# edlinv.net
KiCad netlist of a schematic drawn in EAGLE
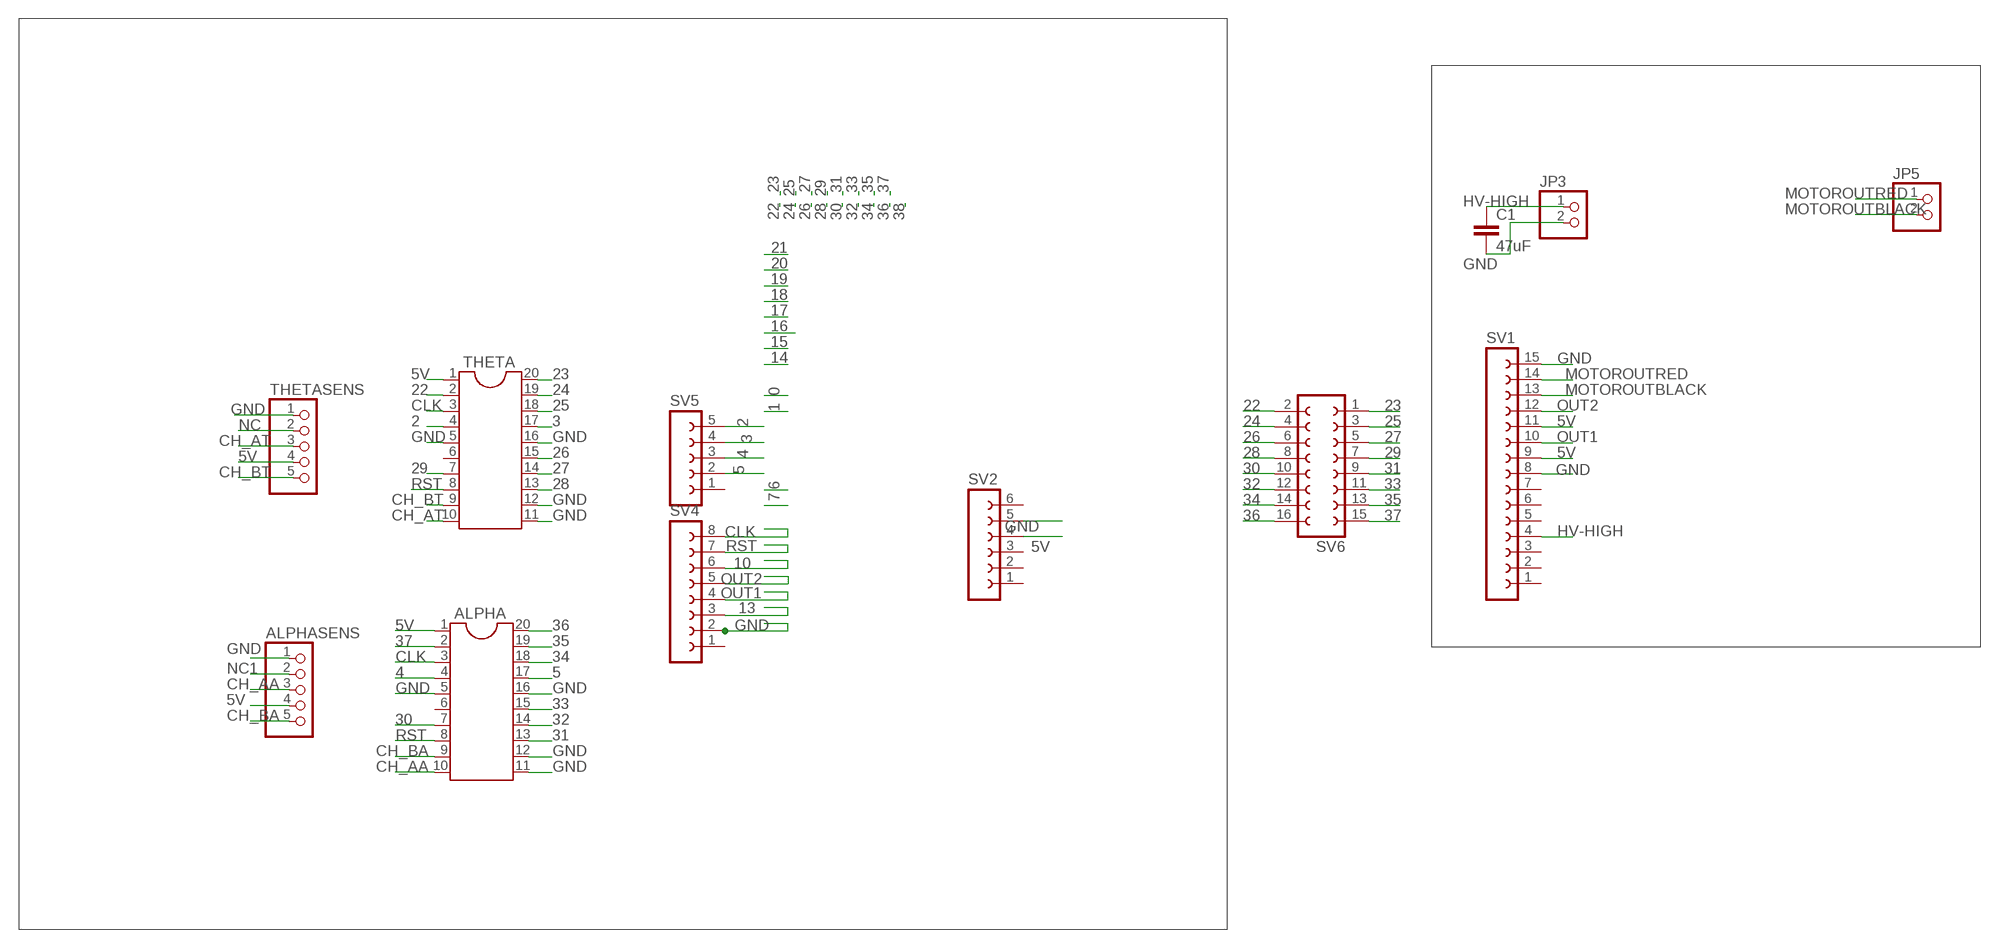
[diagram p0: schematic, sheet 1]

(export (version "E")
  (design (tool "Eeschema 10.0.6"))
  (components
    (comp (ref "ALPHA")
      (value "DIL20")
      (footprint "eagle-import:DIL20")
      (libsource (lib "eagle-import") (part "DIL20"))
    )
    (comp (ref "ALPHASENS")
      (value "PINHD-1X5")
      (footprint "eagle-import:1X05")
      (libsource (lib "eagle-import") (part "PINHD-1X5"))
    )
    (comp (ref "C1")
      (value "47uF")
      (footprint "eagle-import:C025-025X050")
      (libsource (lib "eagle-import") (part "C-EU025-025X050"))
    )
    (comp (ref "JP3")
      (value "PINHD-1X2")
      (footprint "eagle-import:1X02")
      (libsource (lib "eagle-import") (part "PINHD-1X2"))
    )
    (comp (ref "JP5")
      (value "PINHD-1X2")
      (footprint "eagle-import:1X02")
      (libsource (lib "eagle-import") (part "PINHD-1X2"))
    )
    (comp (ref "SV1")
      (value "FE15-1")
      (footprint "eagle-import:FE15")
      (libsource (lib "eagle-import") (part "FE15-1"))
    )
    (comp (ref "SV2")
      (value "FE06-1")
      (footprint "eagle-import:FE06")
      (libsource (lib "eagle-import") (part "FE06-1"))
    )
    (comp (ref "SV4")
      (value "FE08-1")
      (footprint "eagle-import:FE08")
      (libsource (lib "eagle-import") (part "FE08-1"))
    )
    (comp (ref "SV5")
      (value "FE05-1")
      (footprint "eagle-import:FE05-1")
      (libsource (lib "eagle-import") (part "FE05-1"))
    )
    (comp (ref "SV6")
      (value "FE08-2")
      (footprint "eagle-import:FE08-2")
      (libsource (lib "eagle-import") (part "FE08-2"))
    )
    (comp (ref "THETA")
      (value "DIL20")
      (footprint "eagle-import:DIL20")
      (libsource (lib "eagle-import") (part "DIL20"))
    )
    (comp (ref "THETASENS")
      (value "PINHD-1X5")
      (footprint "eagle-import:1X05")
      (libsource (lib "eagle-import") (part "PINHD-1X5"))
    )
  )
  (nets
    (net (code "3") (name "/2") (class "Default")
      (node (ref "SV5") (pin "5") (pinfunction "5_5") (pintype "passive"))
      (node (ref "THETA") (pin "4") (pinfunction "4_4") (pintype "passive"))
    )
    (net (code "4") (name "/3") (class "Default")
      (node (ref "SV5") (pin "4") (pinfunction "4_4") (pintype "passive"))
      (node (ref "THETA") (pin "17") (pinfunction "17_17") (pintype "passive"))
    )
    (net (code "5") (name "/4") (class "Default")
      (node (ref "ALPHA") (pin "4") (pinfunction "4_4") (pintype "passive"))
      (node (ref "SV5") (pin "3") (pinfunction "3_3") (pintype "passive"))
    )
    (net (code "6") (name "/5") (class "Default")
      (node (ref "ALPHA") (pin "17") (pinfunction "17_17") (pintype "passive"))
      (node (ref "SV5") (pin "2") (pinfunction "2_2") (pintype "passive"))
    )
    (net (code "7") (name "/5V") (class "Default")
      (node (ref "ALPHA") (pin "1") (pinfunction "1_1") (pintype "passive"))
      (node (ref "ALPHASENS") (pin "4") (pinfunction "4_4") (pintype "passive"))
      (node (ref "SV1") (pin "11") (pinfunction "11_11") (pintype "passive"))
      (node (ref "SV1") (pin "9") (pinfunction "9_9") (pintype "passive"))
      (node (ref "SV2") (pin "4") (pinfunction "4_4") (pintype "passive"))
      (node (ref "THETA") (pin "1") (pinfunction "1_1") (pintype "passive"))
      (node (ref "THETASENS") (pin "4") (pinfunction "4_4") (pintype "passive"))
    )
    (net (code "10") (name "/10") (class "Default")
      (node (ref "SV4") (pin "6") (pinfunction "6_6") (pintype "passive"))
    )
    (net (code "11") (name "/13") (class "Default")
      (node (ref "SV4") (pin "3") (pinfunction "3_3") (pintype "passive"))
    )
    (net (code "20") (name "/22") (class "Default")
      (node (ref "SV6") (pin "2") (pinfunction "2_2") (pintype "passive"))
      (node (ref "THETA") (pin "2") (pinfunction "2_2") (pintype "passive"))
    )
    (net (code "21") (name "/23") (class "Default")
      (node (ref "SV6") (pin "1") (pinfunction "1_1") (pintype "passive"))
      (node (ref "THETA") (pin "20") (pinfunction "20_20") (pintype "passive"))
    )
    (net (code "22") (name "/24") (class "Default")
      (node (ref "SV6") (pin "4") (pinfunction "4_4") (pintype "passive"))
      (node (ref "THETA") (pin "19") (pinfunction "19_19") (pintype "passive"))
    )
    (net (code "23") (name "/25") (class "Default")
      (node (ref "SV6") (pin "3") (pinfunction "3_3") (pintype "passive"))
      (node (ref "THETA") (pin "18") (pinfunction "18_18") (pintype "passive"))
    )
    (net (code "24") (name "/26") (class "Default")
      (node (ref "SV6") (pin "6") (pinfunction "6_6") (pintype "passive"))
      (node (ref "THETA") (pin "15") (pinfunction "15_15") (pintype "passive"))
    )
    (net (code "25") (name "/27") (class "Default")
      (node (ref "SV6") (pin "5") (pinfunction "5_5") (pintype "passive"))
      (node (ref "THETA") (pin "14") (pinfunction "14_14") (pintype "passive"))
    )
    (net (code "26") (name "/28") (class "Default")
      (node (ref "SV6") (pin "8") (pinfunction "8_8") (pintype "passive"))
      (node (ref "THETA") (pin "13") (pinfunction "13_13") (pintype "passive"))
    )
    (net (code "27") (name "/29") (class "Default")
      (node (ref "SV6") (pin "7") (pinfunction "7_7") (pintype "passive"))
      (node (ref "THETA") (pin "7") (pinfunction "7_7") (pintype "passive"))
    )
    (net (code "28") (name "/30") (class "Default")
      (node (ref "ALPHA") (pin "7") (pinfunction "7_7") (pintype "passive"))
      (node (ref "SV6") (pin "10") (pinfunction "10_10") (pintype "passive"))
    )
    (net (code "29") (name "/31") (class "Default")
      (node (ref "ALPHA") (pin "13") (pinfunction "13_13") (pintype "passive"))
      (node (ref "SV6") (pin "9") (pinfunction "9_9") (pintype "passive"))
    )
    (net (code "30") (name "/32") (class "Default")
      (node (ref "ALPHA") (pin "14") (pinfunction "14_14") (pintype "passive"))
      (node (ref "SV6") (pin "12") (pinfunction "12_12") (pintype "passive"))
    )
    (net (code "31") (name "/33") (class "Default")
      (node (ref "ALPHA") (pin "15") (pinfunction "15_15") (pintype "passive"))
      (node (ref "SV6") (pin "11") (pinfunction "11_11") (pintype "passive"))
    )
    (net (code "32") (name "/34") (class "Default")
      (node (ref "ALPHA") (pin "18") (pinfunction "18_18") (pintype "passive"))
      (node (ref "SV6") (pin "14") (pinfunction "14_14") (pintype "passive"))
    )
    (net (code "33") (name "/35") (class "Default")
      (node (ref "ALPHA") (pin "19") (pinfunction "19_19") (pintype "passive"))
      (node (ref "SV6") (pin "13") (pinfunction "13_13") (pintype "passive"))
    )
    (net (code "34") (name "/36") (class "Default")
      (node (ref "ALPHA") (pin "20") (pinfunction "20_20") (pintype "passive"))
      (node (ref "SV6") (pin "16") (pinfunction "16_16") (pintype "passive"))
    )
    (net (code "35") (name "/37") (class "Default")
      (node (ref "ALPHA") (pin "2") (pinfunction "2_2") (pintype "passive"))
      (node (ref "SV6") (pin "15") (pinfunction "15_15") (pintype "passive"))
    )
    (net (code "37") (name "/CH_AA") (class "Default")
      (node (ref "ALPHA") (pin "10") (pinfunction "10_10") (pintype "passive"))
      (node (ref "ALPHASENS") (pin "3") (pinfunction "3_3") (pintype "passive"))
    )
    (net (code "38") (name "/CH_AT") (class "Default")
      (node (ref "THETA") (pin "10") (pinfunction "10_10") (pintype "passive"))
      (node (ref "THETASENS") (pin "3") (pinfunction "3_3") (pintype "passive"))
    )
    (net (code "39") (name "/CH_BA") (class "Default")
      (node (ref "ALPHA") (pin "9") (pinfunction "9_9") (pintype "passive"))
      (node (ref "ALPHASENS") (pin "5") (pinfunction "5_5") (pintype "passive"))
    )
    (net (code "40") (name "/CH_BT") (class "Default")
      (node (ref "THETA") (pin "9") (pinfunction "9_9") (pintype "passive"))
      (node (ref "THETASENS") (pin "5") (pinfunction "5_5") (pintype "passive"))
    )
    (net (code "41") (name "/CLK") (class "Default")
      (node (ref "ALPHA") (pin "3") (pinfunction "3_3") (pintype "passive"))
      (node (ref "SV4") (pin "8") (pinfunction "8_8") (pintype "passive"))
      (node (ref "THETA") (pin "3") (pinfunction "3_3") (pintype "passive"))
    )
    (net (code "42") (name "/GND") (class "Default")
      (node (ref "ALPHA") (pin "11") (pinfunction "11_11") (pintype "passive"))
      (node (ref "ALPHA") (pin "12") (pinfunction "12_12") (pintype "passive"))
      (node (ref "ALPHA") (pin "16") (pinfunction "16_16") (pintype "passive"))
      (node (ref "ALPHA") (pin "5") (pinfunction "5_5") (pintype "passive"))
      (node (ref "ALPHASENS") (pin "1") (pinfunction "1_1") (pintype "passive"))
      (node (ref "C1") (pin "2") (pinfunction "2_2") (pintype "passive"))
      (node (ref "JP3") (pin "2") (pinfunction "2_2") (pintype "passive"))
      (node (ref "SV1") (pin "15") (pinfunction "15_15") (pintype "passive"))
      (node (ref "SV1") (pin "8") (pinfunction "8_8") (pintype "passive"))
      (node (ref "SV2") (pin "5") (pinfunction "5_5") (pintype "passive"))
      (node (ref "SV4") (pin "2") (pinfunction "2_2") (pintype "passive"))
      (node (ref "THETA") (pin "11") (pinfunction "11_11") (pintype "passive"))
      (node (ref "THETA") (pin "12") (pinfunction "12_12") (pintype "passive"))
      (node (ref "THETA") (pin "16") (pinfunction "16_16") (pintype "passive"))
      (node (ref "THETA") (pin "5") (pinfunction "5_5") (pintype "passive"))
      (node (ref "THETASENS") (pin "1") (pinfunction "1_1") (pintype "passive"))
    )
    (net (code "43") (name "/HV-HIGH") (class "Default")
      (node (ref "C1") (pin "1") (pinfunction "1_1") (pintype "passive"))
      (node (ref "JP3") (pin "1") (pinfunction "1_1") (pintype "passive"))
      (node (ref "SV1") (pin "4") (pinfunction "4_4") (pintype "passive"))
    )
    (net (code "44") (name "/MOTOROUTBLACK") (class "Default")
      (node (ref "JP5") (pin "2") (pinfunction "2_2") (pintype "passive"))
      (node (ref "SV1") (pin "13") (pinfunction "13_13") (pintype "passive"))
    )
    (net (code "45") (name "/MOTOROUTRED") (class "Default")
      (node (ref "JP5") (pin "1") (pinfunction "1_1") (pintype "passive"))
      (node (ref "SV1") (pin "14") (pinfunction "14_14") (pintype "passive"))
    )
    (net (code "46") (name "/NC") (class "Default")
      (node (ref "THETASENS") (pin "2") (pinfunction "2_2") (pintype "passive"))
    )
    (net (code "47") (name "/NC1") (class "Default")
      (node (ref "ALPHASENS") (pin "2") (pinfunction "2_2") (pintype "passive"))
    )
    (net (code "48") (name "/OUT1") (class "Default")
      (node (ref "SV1") (pin "10") (pinfunction "10_10") (pintype "passive"))
      (node (ref "SV4") (pin "4") (pinfunction "4_4") (pintype "passive"))
    )
    (net (code "49") (name "/OUT2") (class "Default")
      (node (ref "SV1") (pin "12") (pinfunction "12_12") (pintype "passive"))
      (node (ref "SV4") (pin "5") (pinfunction "5_5") (pintype "passive"))
    )
    (net (code "50") (name "/RST") (class "Default")
      (node (ref "ALPHA") (pin "8") (pinfunction "8_8") (pintype "passive"))
      (node (ref "SV4") (pin "7") (pinfunction "7_7") (pintype "passive"))
      (node (ref "THETA") (pin "8") (pinfunction "8_8") (pintype "passive"))
    )
    (net (code "51") (name "unconnected-(ALPHA-Pad6)") (class "Default")
      (node (ref "ALPHA") (pin "6") (pinfunction "6_6") (pintype "passive"))
    )
    (net (code "52") (name "unconnected-(SV1-Pad1)") (class "Default")
      (node (ref "SV1") (pin "1") (pinfunction "1_1") (pintype "passive"))
    )
    (net (code "53") (name "unconnected-(SV1-Pad2)") (class "Default")
      (node (ref "SV1") (pin "2") (pinfunction "2_2") (pintype "passive"))
    )
    (net (code "54") (name "unconnected-(SV1-Pad3)") (class "Default")
      (node (ref "SV1") (pin "3") (pinfunction "3_3") (pintype "passive"))
    )
    (net (code "55") (name "unconnected-(SV1-Pad5)") (class "Default")
      (node (ref "SV1") (pin "5") (pinfunction "5_5") (pintype "passive"))
    )
    (net (code "56") (name "unconnected-(SV1-Pad6)") (class "Default")
      (node (ref "SV1") (pin "6") (pinfunction "6_6") (pintype "passive"))
    )
    (net (code "57") (name "unconnected-(SV1-Pad7)") (class "Default")
      (node (ref "SV1") (pin "7") (pinfunction "7_7") (pintype "passive"))
    )
    (net (code "58") (name "unconnected-(SV2-Pad1)") (class "Default")
      (node (ref "SV2") (pin "1") (pinfunction "1_1") (pintype "passive"))
    )
    (net (code "59") (name "unconnected-(SV2-Pad2)") (class "Default")
      (node (ref "SV2") (pin "2") (pinfunction "2_2") (pintype "passive"))
    )
    (net (code "60") (name "unconnected-(SV2-Pad3)") (class "Default")
      (node (ref "SV2") (pin "3") (pinfunction "3_3") (pintype "passive"))
    )
    (net (code "61") (name "unconnected-(SV2-Pad6)") (class "Default")
      (node (ref "SV2") (pin "6") (pinfunction "6_6") (pintype "passive"))
    )
    (net (code "62") (name "unconnected-(SV4-Pad1)") (class "Default")
      (node (ref "SV4") (pin "1") (pinfunction "1_1") (pintype "passive"))
    )
    (net (code "63") (name "unconnected-(SV5-Pad1)") (class "Default")
      (node (ref "SV5") (pin "1") (pinfunction "1_1") (pintype "passive"))
    )
    (net (code "64") (name "unconnected-(THETA-Pad6)") (class "Default")
      (node (ref "THETA") (pin "6") (pinfunction "6_6") (pintype "passive"))
    )
  )
)
